# rc-driver-programmer.net
KiCad netlist of a schematic drawn in EAGLE
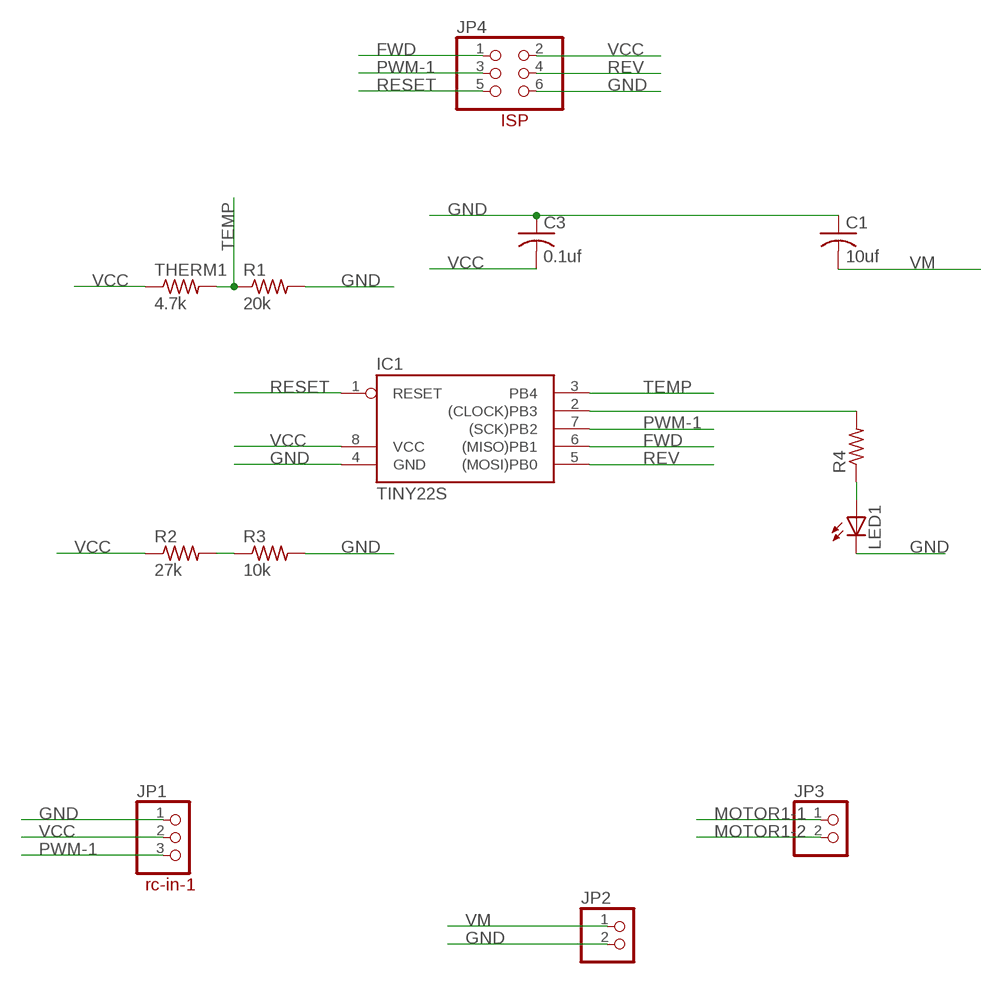
[diagram p0: schematic, sheet 1]

(export (version "E")
  (design (tool "Eeschema 10.0.6"))
  (components
    (comp (ref "C1")
      (value "10uf")
      (footprint "eagle-import:C1210")
      (libsource (lib "eagle-import") (part "C-USC1210"))
    )
    (comp (ref "C3")
      (value "0.1uf")
      (footprint "eagle-import:C0805")
      (libsource (lib "eagle-import") (part "C-USC0805"))
    )
    (comp (ref "IC1")
      (value "TINY22S")
      (footprint "eagle-import:SOIC8")
      (libsource (lib "eagle-import") (part "TINY22S"))
    )
    (comp (ref "JP1")
      (value "PINHD-1X3")
      (footprint "eagle-import:1X03")
      (libsource (lib "eagle-import") (part "PINHD-1X3"))
    )
    (comp (ref "JP2")
      (value "PINHD-1X2")
      (footprint "eagle-import:1X02")
      (libsource (lib "eagle-import") (part "PINHD-1X2"))
    )
    (comp (ref "JP3")
      (value "PINHD-1X2")
      (footprint "eagle-import:1X02")
      (libsource (lib "eagle-import") (part "PINHD-1X2"))
    )
    (comp (ref "JP4")
      (value "PINHD-2X3")
      (footprint "eagle-import:2X03")
      (libsource (lib "eagle-import") (part "PINHD-2X3"))
    )
    (comp (ref "LED1")
      (value "LEDCHIP-LED0603")
      (footprint "eagle-import:CHIP-LED0603")
      (libsource (lib "eagle-import") (part "LEDCHIP-LED0603"))
    )
    (comp (ref "R1")
      (value "20k")
      (footprint "eagle-import:R0603")
      (libsource (lib "eagle-import") (part "R-US_R0603"))
    )
    (comp (ref "R2")
      (value "27k")
      (footprint "eagle-import:R0603")
      (libsource (lib "eagle-import") (part "R-US_R0603"))
    )
    (comp (ref "R3")
      (value "10k")
      (footprint "eagle-import:R0603")
      (libsource (lib "eagle-import") (part "R-US_R0603"))
    )
    (comp (ref "R4")
      (value "R-US_R0603")
      (footprint "eagle-import:R0603")
      (libsource (lib "eagle-import") (part "R-US_R0603"))
    )
    (comp (ref "THERM1")
      (value "4.7k")
      (footprint "eagle-import:R0603")
      (libsource (lib "eagle-import") (part "R-US_R0603"))
    )
  )
  (nets
    (net (code "1") (name "/FWD") (class "Default")
      (node (ref "IC1") (pin "6") (pinfunction "(MISO)PB1_6") (pintype "bidirectional"))
      (node (ref "JP4") (pin "1") (pinfunction "1_1") (pintype "passive"))
    )
    (net (code "2") (name "/GND") (class "Default")
      (node (ref "C1") (pin "1") (pinfunction "1_1") (pintype "passive"))
      (node (ref "C3") (pin "1") (pinfunction "1_1") (pintype "passive"))
      (node (ref "IC1") (pin "4") (pinfunction "GND_4") (pintype "power_in"))
      (node (ref "JP1") (pin "1") (pinfunction "1_1") (pintype "passive"))
      (node (ref "JP2") (pin "2") (pinfunction "2_2") (pintype "passive"))
      (node (ref "JP4") (pin "6") (pinfunction "6_6") (pintype "passive"))
      (node (ref "LED1") (pin "C") (pinfunction "C_C") (pintype "passive"))
      (node (ref "R1") (pin "2") (pinfunction "2_2") (pintype "passive"))
      (node (ref "R3") (pin "2") (pinfunction "2_2") (pintype "passive"))
    )
    (net (code "3") (name "/MOTOR1-1") (class "Default")
      (node (ref "JP3") (pin "1") (pinfunction "1_1") (pintype "passive"))
    )
    (net (code "4") (name "/MOTOR1-2") (class "Default")
      (node (ref "JP3") (pin "2") (pinfunction "2_2") (pintype "passive"))
    )
    (net (code "5") (name "/PWM-1") (class "Default")
      (node (ref "IC1") (pin "7") (pinfunction "(SCK)PB2_7") (pintype "bidirectional"))
      (node (ref "JP1") (pin "3") (pinfunction "3_3") (pintype "passive"))
      (node (ref "JP4") (pin "3") (pinfunction "3_3") (pintype "passive"))
    )
    (net (code "6") (name "/RESET") (class "Default")
      (node (ref "IC1") (pin "1") (pinfunction "RESET_1") (pintype "input"))
      (node (ref "JP4") (pin "5") (pinfunction "5_5") (pintype "passive"))
    )
    (net (code "7") (name "/REV") (class "Default")
      (node (ref "IC1") (pin "5") (pinfunction "(MOSI)PB0_5") (pintype "bidirectional"))
      (node (ref "JP4") (pin "4") (pinfunction "4_4") (pintype "passive"))
    )
    (net (code "8") (name "/TEMP") (class "Default")
      (node (ref "IC1") (pin "3") (pinfunction "PB4_3") (pintype "bidirectional"))
      (node (ref "R1") (pin "1") (pinfunction "1_1") (pintype "passive"))
      (node (ref "THERM1") (pin "2") (pinfunction "2_2") (pintype "passive"))
    )
    (net (code "9") (name "/VCC") (class "Default")
      (node (ref "C3") (pin "2") (pinfunction "2_2") (pintype "passive"))
      (node (ref "IC1") (pin "8") (pinfunction "VCC_8") (pintype "power_in"))
      (node (ref "JP1") (pin "2") (pinfunction "2_2") (pintype "passive"))
      (node (ref "JP4") (pin "2") (pinfunction "2_2") (pintype "passive"))
      (node (ref "R2") (pin "1") (pinfunction "1_1") (pintype "passive"))
      (node (ref "THERM1") (pin "1") (pinfunction "1_1") (pintype "passive"))
    )
    (net (code "10") (name "/VM") (class "Default")
      (node (ref "C1") (pin "2") (pinfunction "2_2") (pintype "passive"))
      (node (ref "JP2") (pin "1") (pinfunction "1_1") (pintype "passive"))
    )
    (net (code "11") (name "Net-(IC1-(CLOCK)PB3)") (class "Default")
      (node (ref "IC1") (pin "2") (pinfunction "(CLOCK)PB3_2") (pintype "bidirectional"))
      (node (ref "R4") (pin "2") (pinfunction "2_2") (pintype "passive"))
    )
    (net (code "12") (name "Net-(LED1-PadA)") (class "Default")
      (node (ref "LED1") (pin "A") (pinfunction "A_A") (pintype "passive"))
      (node (ref "R4") (pin "1") (pinfunction "1_1") (pintype "passive"))
    )
    (net (code "13") (name "Net-(R2-Pad2)") (class "Default")
      (node (ref "R2") (pin "2") (pinfunction "2_2") (pintype "passive"))
      (node (ref "R3") (pin "1") (pinfunction "1_1") (pintype "passive"))
    )
  )
)
